# PERIPHERAL.net
KiCad netlist of a schematic drawn in Altium Designer
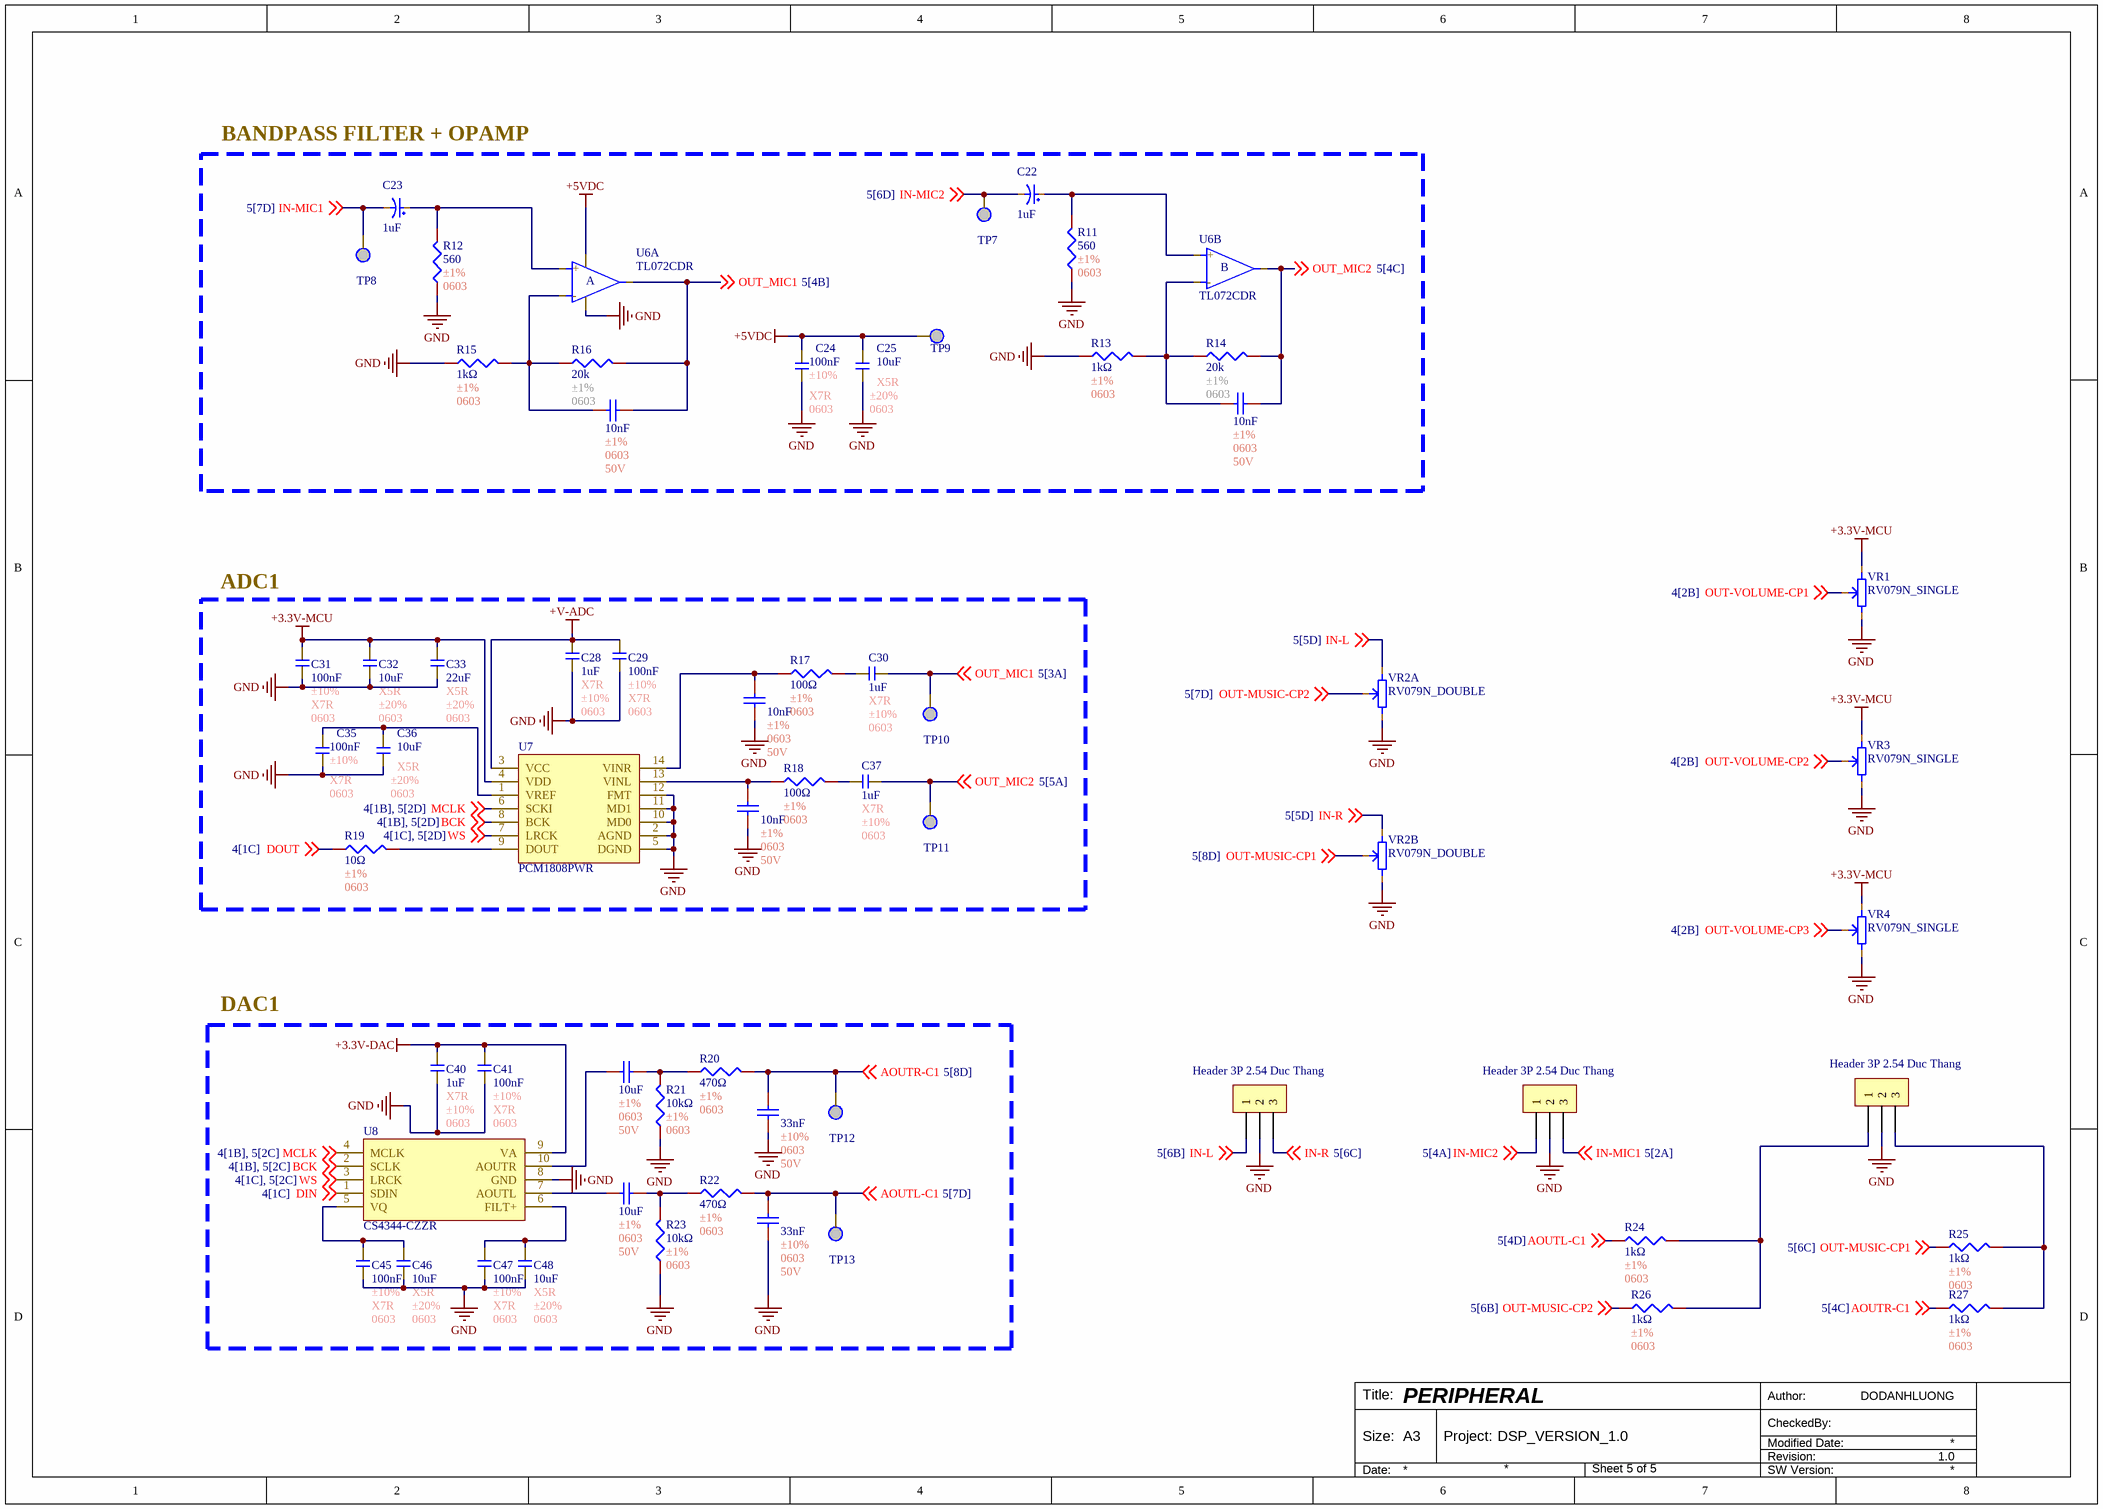
[diagram p0: PERIPHERAL.SchDoc]

(export (version "E")
  (design (tool "Eeschema 10.0.6"))
  (components
    (comp (ref "C22")
      (value "1uF")
      (footprint "C_TH_5x11mm")
      (description "10uF 50V ±20% Through Hole,D5xL11mm Aluminum Electrolytic Capacitors - Leaded ROHS")
      (fields (field (name "MANUFACTURER") "Rubycon") (field (name "MFR. PART #") "50YXF10MEFC5X11"))
      (libsource (lib "Capital") (part "C_10uF_5x11TH"))
    )
    (comp (ref "C23")
      (value "1uF")
      (footprint "C_TH_5x11mm")
      (description "10uF 50V ±20% Through Hole,D5xL11mm Aluminum Electrolytic Capacitors - Leaded ROHS")
      (fields (field (name "MANUFACTURER") "Rubycon") (field (name "MFR. PART #") "50YXF10MEFC5X11"))
      (libsource (lib "Capital") (part "C_10uF_5x11TH"))
    )
    (comp (ref "C24")
      (value "100nF")
      (footprint "C0603")
      (description "50V 100nF X7R ±10% 0603 Multilayer Ceramic Capacitors MLCC - SMD/SMT ROHS")
      (fields
        (field (name "MANUFACTURER") "YAGEO")
        (field (name "MFR. PART #") "CC0603KRX7R9BB104")
        (field (name "TOLERANCE") "±10%")
        (field (name "TEMPERATURE COEFFICIENT") "X7R")
        (field (name "PACKAGE") "0603")
      )
      (libsource (lib "DSP_VERSION_1.0") (part "C0603_100nF_±10%_X7R"))
    )
    (comp (ref "C25")
      (value "10uF")
      (footprint "C0603")
      (description "25V 10uF X5R ±20% 0603 Multilayer Ceramic Capacitors MLCC - SMD/SMT ROHS")
      (fields
        (field (name "MANUFACTURER") "YAGEO")
        (field (name "MFR. PART #") "CC0603MRX5R8BB106")
        (field (name "TEMPERATURE COEFFICIENT") "X5R")
        (field (name "TOLERANCE") "±20%")
        (field (name "PACKAGE") "0603")
      )
      (libsource (lib "DSP_VERSION_1.0") (part "C0603_10uF_±10%_X7R"))
    )
    (comp (ref "C26")
      (value "10nF")
      (footprint "C0603")
      (description "50V 10pF NP0 ±1% 0402 Multilayer Ceramic Capacitors MLCC - SMD/SMT ROHS")
      (fields
        (field (name "MANUFACTURER") "YAGEO")
        (field (name "MFR. PART #") "CC0402FRNPO9BN100")
        (field (name "TOLERANCE") "±1%")
        (field (name "PACKAGE") "0603")
        (field (name "VOLTAGE RATING") "50V")
      )
      (libsource (lib "Capital") (part "C0603_10nF_±1%"))
    )
    (comp (ref "C27")
      (value "10nF")
      (footprint "C0603")
      (description "50V 10pF NP0 ±1% 0402 Multilayer Ceramic Capacitors MLCC - SMD/SMT ROHS")
      (fields
        (field (name "MANUFACTURER") "YAGEO")
        (field (name "MFR. PART #") "CC0402FRNPO9BN100")
        (field (name "TOLERANCE") "±1%")
        (field (name "PACKAGE") "0603")
        (field (name "VOLTAGE RATING") "50V")
      )
      (libsource (lib "Capital") (part "C0603_10nF_±1%"))
    )
    (comp (ref "C28")
      (value "1uF")
      (footprint "C0603")
      (description "50V 1uF X7R ±10% 0603 Multilayer Ceramic Capacitors MLCC - SMD/SMT ROHS")
      (fields
        (field (name "MANUFACTURER") "YAGEO")
        (field (name "MFR. PART #") "CC0603KRX7R9BB105")
        (field (name "TEMPERATURE COEFFICIENT") "X7R")
        (field (name "TOLERANCE") "±10%")
        (field (name "PACKAGE") "0603")
      )
      (libsource (lib "DSP_VERSION_1.0") (part "C0603_1uF_±10%_X7R"))
    )
    (comp (ref "C29")
      (value "100nF")
      (footprint "C0603")
      (description "50V 100nF X7R ±10% 0603 Multilayer Ceramic Capacitors MLCC - SMD/SMT ROHS")
      (fields
        (field (name "MANUFACTURER") "YAGEO")
        (field (name "MFR. PART #") "CC0603KRX7R9BB104")
        (field (name "TOLERANCE") "±10%")
        (field (name "TEMPERATURE COEFFICIENT") "X7R")
        (field (name "PACKAGE") "0603")
      )
      (libsource (lib "DSP_VERSION_1.0") (part "C0603_100nF_±10%_X7R"))
    )
    (comp (ref "C30")
      (value "1uF")
      (footprint "C0603")
      (description "50V 1uF X7R ±10% 0603 Multilayer Ceramic Capacitors MLCC - SMD/SMT ROHS")
      (fields
        (field (name "MANUFACTURER") "YAGEO")
        (field (name "MFR. PART #") "CC0603KRX7R9BB105")
        (field (name "TEMPERATURE COEFFICIENT") "X7R")
        (field (name "TOLERANCE") "±10%")
        (field (name "PACKAGE") "0603")
      )
      (libsource (lib "DSP_VERSION_1.0") (part "C0603_1uF_±10%_X7R"))
    )
    (comp (ref "C31")
      (value "100nF")
      (footprint "C0603")
      (description "50V 100nF X7R ±10% 0603 Multilayer Ceramic Capacitors MLCC - SMD/SMT ROHS")
      (fields
        (field (name "MANUFACTURER") "YAGEO")
        (field (name "MFR. PART #") "CC0603KRX7R9BB104")
        (field (name "TOLERANCE") "±10%")
        (field (name "TEMPERATURE COEFFICIENT") "X7R")
        (field (name "PACKAGE") "0603")
      )
      (libsource (lib "DSP_VERSION_1.0") (part "C0603_100nF_±10%_X7R"))
    )
    (comp (ref "C32")
      (value "10uF")
      (footprint "C0603")
      (description "25V 10uF X5R ±20% 0603 Multilayer Ceramic Capacitors MLCC - SMD/SMT ROHS")
      (fields
        (field (name "MANUFACTURER") "YAGEO")
        (field (name "MFR. PART #") "CC0603MRX5R8BB106")
        (field (name "TEMPERATURE COEFFICIENT") "X5R")
        (field (name "TOLERANCE") "±20%")
        (field (name "PACKAGE") "0603")
      )
      (libsource (lib "DSP_VERSION_1.0") (part "C0603_10uF_±10%_X7R"))
    )
    (comp (ref "C33")
      (value "22uF")
      (footprint "C0603")
      (description "6.3V 22uF X5R ±20% 0603 Multilayer Ceramic Capacitors MLCC - SMD/SMT ROHS")
      (fields
        (field (name "MANUFACTURER") "YAGEO")
        (field (name "MFR. PART #") "CC0603MRX5R5BB226")
        (field (name "TEMPERATURE COEFFICIENT") "X5R")
        (field (name "TOLERANCE") "±20%")
        (field (name "PACKAGE") "0603")
      )
      (libsource (lib "DSP_VERSION_1.0") (part "C0603_22uF_±20%_X5R"))
    )
    (comp (ref "C34")
      (value "10nF")
      (footprint "C0603")
      (description "50V 10pF NP0 ±1% 0402 Multilayer Ceramic Capacitors MLCC - SMD/SMT ROHS")
      (fields
        (field (name "MANUFACTURER") "YAGEO")
        (field (name "MFR. PART #") "CC0402FRNPO9BN100")
        (field (name "TOLERANCE") "±1%")
        (field (name "PACKAGE") "0603")
        (field (name "VOLTAGE RATING") "50V")
      )
      (libsource (lib "Capital") (part "C0603_10nF_±1%"))
    )
    (comp (ref "C35")
      (value "100nF")
      (footprint "C0603")
      (description "50V 100nF X7R ±10% 0603 Multilayer Ceramic Capacitors MLCC - SMD/SMT ROHS")
      (fields
        (field (name "MANUFACTURER") "YAGEO")
        (field (name "MFR. PART #") "CC0603KRX7R9BB104")
        (field (name "TOLERANCE") "±10%")
        (field (name "TEMPERATURE COEFFICIENT") "X7R")
        (field (name "PACKAGE") "0603")
      )
      (libsource (lib "DSP_VERSION_1.0") (part "C0603_100nF_±10%_X7R"))
    )
    (comp (ref "C36")
      (value "10uF")
      (footprint "C0603")
      (description "25V 10uF X5R ±20% 0603 Multilayer Ceramic Capacitors MLCC - SMD/SMT ROHS")
      (fields
        (field (name "MANUFACTURER") "YAGEO")
        (field (name "MFR. PART #") "CC0603MRX5R8BB106")
        (field (name "TEMPERATURE COEFFICIENT") "X5R")
        (field (name "TOLERANCE") "±20%")
        (field (name "PACKAGE") "0603")
      )
      (libsource (lib "DSP_VERSION_1.0") (part "C0603_10uF_±10%_X7R"))
    )
    (comp (ref "C37")
      (value "1uF")
      (footprint "C0603")
      (description "50V 1uF X7R ±10% 0603 Multilayer Ceramic Capacitors MLCC - SMD/SMT ROHS")
      (fields
        (field (name "MANUFACTURER") "YAGEO")
        (field (name "MFR. PART #") "CC0603KRX7R9BB105")
        (field (name "TEMPERATURE COEFFICIENT") "X7R")
        (field (name "TOLERANCE") "±10%")
        (field (name "PACKAGE") "0603")
      )
      (libsource (lib "DSP_VERSION_1.0") (part "C0603_1uF_±10%_X7R"))
    )
    (comp (ref "C38")
      (value "10nF")
      (footprint "C0603")
      (description "50V 10pF NP0 ±1% 0402 Multilayer Ceramic Capacitors MLCC - SMD/SMT ROHS")
      (fields
        (field (name "MANUFACTURER") "YAGEO")
        (field (name "MFR. PART #") "CC0402FRNPO9BN100")
        (field (name "TOLERANCE") "±1%")
        (field (name "PACKAGE") "0603")
        (field (name "VOLTAGE RATING") "50V")
      )
      (libsource (lib "Capital") (part "C0603_10nF_±1%"))
    )
    (comp (ref "C39")
      (value "10uF")
      (footprint "C0603")
      (description "50V 10pF NP0 ±1% 0402 Multilayer Ceramic Capacitors MLCC - SMD/SMT ROHS")
      (fields
        (field (name "MANUFACTURER") "YAGEO")
        (field (name "MFR. PART #") "CC0402FRNPO9BN100")
        (field (name "TOLERANCE") "±1%")
        (field (name "PACKAGE") "0603")
        (field (name "VOLTAGE RATING") "50V")
      )
      (libsource (lib "Capital") (part "C0603_10uF_±1%"))
    )
    (comp (ref "C40")
      (value "1uF")
      (footprint "C0603")
      (description "50V 1uF X7R ±10% 0603 Multilayer Ceramic Capacitors MLCC - SMD/SMT ROHS")
      (fields
        (field (name "MANUFACTURER") "YAGEO")
        (field (name "MFR. PART #") "CC0603KRX7R9BB105")
        (field (name "TEMPERATURE COEFFICIENT") "X7R")
        (field (name "TOLERANCE") "±10%")
        (field (name "PACKAGE") "0603")
      )
      (libsource (lib "DSP_VERSION_1.0") (part "C0603_1uF_±10%_X7R"))
    )
    (comp (ref "C41")
      (value "100nF")
      (footprint "C0603")
      (description "50V 100nF X7R ±10% 0603 Multilayer Ceramic Capacitors MLCC - SMD/SMT ROHS")
      (fields
        (field (name "MANUFACTURER") "YAGEO")
        (field (name "MFR. PART #") "CC0603KRX7R9BB104")
        (field (name "TOLERANCE") "±10%")
        (field (name "TEMPERATURE COEFFICIENT") "X7R")
        (field (name "PACKAGE") "0603")
      )
      (libsource (lib "DSP_VERSION_1.0") (part "C0603_100nF_±10%_X7R"))
    )
    (comp (ref "C42")
      (value "33nF")
      (footprint "C0603")
      (description "100mW Thick Film Resistor 75V ±100ppm/℃ ±1% 470Ω 0603 Chip Resistor - Surface Mount ROHS")
      (fields
        (field (name "MANUFACTURER") "YAGEO")
        (field (name "MFR. PART #") "CC0603KRX7R9BB333")
        (field (name "TOLERANCE") "±10%")
        (field (name "PACKAGE") "0603")
        (field (name "VOLTAGE RATING") "50V")
      )
      (libsource (lib "Capital") (part "C0603_33nF_±10%"))
    )
    (comp (ref "C43")
      (value "10uF")
      (footprint "C0603")
      (description "50V 10pF NP0 ±1% 0402 Multilayer Ceramic Capacitors MLCC - SMD/SMT ROHS")
      (fields
        (field (name "MANUFACTURER") "YAGEO")
        (field (name "MFR. PART #") "CC0402FRNPO9BN100")
        (field (name "TOLERANCE") "±1%")
        (field (name "PACKAGE") "0603")
        (field (name "VOLTAGE RATING") "50V")
      )
      (libsource (lib "Capital") (part "C0603_10uF_±1%"))
    )
    (comp (ref "C44")
      (value "33nF")
      (footprint "C0603")
      (description "100mW Thick Film Resistor 75V ±100ppm/℃ ±1% 470Ω 0603 Chip Resistor - Surface Mount ROHS")
      (fields
        (field (name "MANUFACTURER") "YAGEO")
        (field (name "MFR. PART #") "CC0603KRX7R9BB333")
        (field (name "TOLERANCE") "±10%")
        (field (name "PACKAGE") "0603")
        (field (name "VOLTAGE RATING") "50V")
      )
      (libsource (lib "Capital") (part "C0603_33nF_±10%"))
    )
    (comp (ref "C45")
      (value "100nF")
      (footprint "C0603")
      (description "50V 100nF X7R ±10% 0603 Multilayer Ceramic Capacitors MLCC - SMD/SMT ROHS")
      (fields
        (field (name "MANUFACTURER") "YAGEO")
        (field (name "MFR. PART #") "CC0603KRX7R9BB104")
        (field (name "TOLERANCE") "±10%")
        (field (name "TEMPERATURE COEFFICIENT") "X7R")
        (field (name "PACKAGE") "0603")
      )
      (libsource (lib "DSP_VERSION_1.0") (part "C0603_100nF_±10%_X7R"))
    )
    (comp (ref "C46")
      (value "10uF")
      (footprint "C0603")
      (description "25V 10uF X5R ±20% 0603 Multilayer Ceramic Capacitors MLCC - SMD/SMT ROHS")
      (fields
        (field (name "MANUFACTURER") "YAGEO")
        (field (name "MFR. PART #") "CC0603MRX5R8BB106")
        (field (name "TEMPERATURE COEFFICIENT") "X5R")
        (field (name "TOLERANCE") "±20%")
        (field (name "PACKAGE") "0603")
      )
      (libsource (lib "DSP_VERSION_1.0") (part "C0603_10uF_±10%_X7R"))
    )
    (comp (ref "C47")
      (value "100nF")
      (footprint "C0603")
      (description "50V 100nF X7R ±10% 0603 Multilayer Ceramic Capacitors MLCC - SMD/SMT ROHS")
      (fields
        (field (name "MANUFACTURER") "YAGEO")
        (field (name "MFR. PART #") "CC0603KRX7R9BB104")
        (field (name "TOLERANCE") "±10%")
        (field (name "TEMPERATURE COEFFICIENT") "X7R")
        (field (name "PACKAGE") "0603")
      )
      (libsource (lib "DSP_VERSION_1.0") (part "C0603_100nF_±10%_X7R"))
    )
    (comp (ref "C48")
      (value "10uF")
      (footprint "C0603")
      (description "25V 10uF X5R ±20% 0603 Multilayer Ceramic Capacitors MLCC - SMD/SMT ROHS")
      (fields
        (field (name "MANUFACTURER") "YAGEO")
        (field (name "MFR. PART #") "CC0603MRX5R8BB106")
        (field (name "TEMPERATURE COEFFICIENT") "X5R")
        (field (name "TOLERANCE") "±20%")
        (field (name "PACKAGE") "0603")
      )
      (libsource (lib "DSP_VERSION_1.0") (part "C0603_10uF_±10%_X7R"))
    )
    (comp (ref "H1")
      (value "Header 3P 2.54 Duc Thang")
      (footprint "XH2.54M-3")
      (description "Cắm")
      (libsource (lib "Header") (part "Header 3P 2.54 Duc Thang"))
    )
    (comp (ref "H2")
      (value "Header 3P 2.54 Duc Thang")
      (footprint "XH2.54M-3")
      (description "Cắm")
      (libsource (lib "Header") (part "Header 3P 2.54 Duc Thang"))
    )
    (comp (ref "H3")
      (value "Header 3P 2.54 Duc Thang")
      (footprint "XH2.54M-3")
      (description "Cắm")
      (libsource (lib "Header") (part "Header 3P 2.54 Duc Thang"))
    )
    (comp (ref "R11")
      (value "560")
      (footprint "R0603")
      (description "62.5mW Thick Film Resistor 50V ±1% ±200ppm/℃ 10Ω 0402 Chip Resistor - Surface Mount ROHS")
      (fields
        (field (name "MANUFACTURER") "YAGEO")
        (field (name "MFR. PART #") "RC0402FR-0710RL")
        (field (name "TOLERANCE") "±1%")
        (field (name "PACKAGE") "0603")
      )
      (libsource (lib "Resistor") (part "R0603_10kΩ_±1%"))
    )
    (comp (ref "R12")
      (value "560")
      (footprint "R0603")
      (description "62.5mW Thick Film Resistor 50V ±1% ±200ppm/℃ 10Ω 0402 Chip Resistor - Surface Mount ROHS")
      (fields
        (field (name "MANUFACTURER") "YAGEO")
        (field (name "MFR. PART #") "RC0402FR-0710RL")
        (field (name "TOLERANCE") "±1%")
        (field (name "PACKAGE") "0603")
      )
      (libsource (lib "Resistor") (part "R0603_10kΩ_±1%"))
    )
    (comp (ref "R13")
      (value "1kΩ")
      (footprint "R0603")
      (description "62.5mW Thick Film Resistor 50V ±1% ±200ppm/℃ 10Ω 0402 Chip Resistor - Surface Mount ROHS")
      (fields
        (field (name "MANUFACTURER") "YAGEO")
        (field (name "MFR. PART #") "RC0402FR-0710RL")
        (field (name "TOLERANCE") "±1%")
        (field (name "PACKAGE") "0603")
      )
      (libsource (lib "Resistor") (part "R0603_1kΩ_±1%"))
    )
    (comp (ref "R14")
      (value "20k")
      (footprint "R0603")
      (description "100mW Thick Film Resistor 75V ±100ppm/℃ ±1% 5.1kΩ 0603 Chip Resistor - Surface Mount ROHS")
      (fields
        (field (name "MANUFACTURER") "FOJAN")
        (field (name "MFR. PART #") "FRC0603F5101TS")
        (field (name "TOLERANCE") "±1%")
        (field (name "PACKAGE") "0603")
      )
      (libsource (lib "Resistor") (part "R0603_5k1Ω_±1%"))
    )
    (comp (ref "R15")
      (value "1kΩ")
      (footprint "R0603")
      (description "62.5mW Thick Film Resistor 50V ±1% ±200ppm/℃ 10Ω 0402 Chip Resistor - Surface Mount ROHS")
      (fields
        (field (name "MANUFACTURER") "YAGEO")
        (field (name "MFR. PART #") "RC0402FR-0710RL")
        (field (name "TOLERANCE") "±1%")
        (field (name "PACKAGE") "0603")
      )
      (libsource (lib "Resistor") (part "R0603_1kΩ_±1%"))
    )
    (comp (ref "R16")
      (value "20k")
      (footprint "R0603")
      (description "100mW Thick Film Resistor 75V ±100ppm/℃ ±1% 5.1kΩ 0603 Chip Resistor - Surface Mount ROHS")
      (fields
        (field (name "MANUFACTURER") "FOJAN")
        (field (name "MFR. PART #") "FRC0603F5101TS")
        (field (name "TOLERANCE") "±1%")
        (field (name "PACKAGE") "0603")
      )
      (libsource (lib "Resistor") (part "R0603_5k1Ω_±1%"))
    )
    (comp (ref "R17")
      (value "100Ω")
      (footprint "R0603")
      (description "62.5mW Thick Film Resistor 50V ±1% ±200ppm/℃ 10Ω 0402 Chip Resistor - Surface Mount ROHS")
      (fields
        (field (name "MANUFACTURER") "YAGEO")
        (field (name "MFR. PART #") "RC0402FR-0710RL")
        (field (name "TOLERANCE") "±1%")
        (field (name "PACKAGE") "0603")
      )
      (libsource (lib "Resistor") (part "R0603_100Ω_±1%"))
    )
    (comp (ref "R18")
      (value "100Ω")
      (footprint "R0603")
      (description "62.5mW Thick Film Resistor 50V ±1% ±200ppm/℃ 10Ω 0402 Chip Resistor - Surface Mount ROHS")
      (fields
        (field (name "MANUFACTURER") "YAGEO")
        (field (name "MFR. PART #") "RC0402FR-0710RL")
        (field (name "TOLERANCE") "±1%")
        (field (name "PACKAGE") "0603")
      )
      (libsource (lib "Resistor") (part "R0603_100Ω_±1%"))
    )
    (comp (ref "R19")
      (value "10Ω")
      (footprint "R0603")
      (description "62.5mW Thick Film Resistor 50V ±1% ±200ppm/℃ 10Ω 0402 Chip Resistor - Surface Mount ROHS")
      (fields
        (field (name "MANUFACTURER") "YAGEO")
        (field (name "MFR. PART #") "RC0402FR-0710RL")
        (field (name "TOLERANCE") "±1%")
        (field (name "PACKAGE") "0603")
      )
      (libsource (lib "Resistor") (part "R0603_10Ω_±1%"))
    )
    (comp (ref "R20")
      (value "470Ω")
      (footprint "R0603")
      (description "62.5mW Thick Film Resistor 50V ±1% ±200ppm/℃ 10Ω 0402 Chip Resistor - Surface Mount ROHS")
      (fields
        (field (name "MANUFACTURER") "YAGEO")
        (field (name "MFR. PART #") "RC0603FR-07470RL")
        (field (name "TOLERANCE") "±1%")
        (field (name "PACKAGE") "0603")
      )
      (libsource (lib "Resistor") (part "R0603_470Ω_±1%_1"))
    )
    (comp (ref "R21")
      (value "10kΩ")
      (footprint "R0603")
      (description "62.5mW Thick Film Resistor 50V ±1% ±200ppm/℃ 10Ω 0402 Chip Resistor - Surface Mount ROHS")
      (fields
        (field (name "MANUFACTURER") "YAGEO")
        (field (name "MFR. PART #") "RC0402FR-0710RL")
        (field (name "TOLERANCE") "±1%")
        (field (name "PACKAGE") "0603")
      )
      (libsource (lib "Resistor") (part "R0603_10kΩ_±1%"))
    )
    (comp (ref "R22")
      (value "470Ω")
      (footprint "R0603")
      (description "62.5mW Thick Film Resistor 50V ±1% ±200ppm/℃ 10Ω 0402 Chip Resistor - Surface Mount ROHS")
      (fields
        (field (name "MANUFACTURER") "YAGEO")
        (field (name "MFR. PART #") "RC0603FR-07470RL")
        (field (name "TOLERANCE") "±1%")
        (field (name "PACKAGE") "0603")
      )
      (libsource (lib "Resistor") (part "R0603_470Ω_±1%_1"))
    )
    (comp (ref "R23")
      (value "10kΩ")
      (footprint "R0603")
      (description "62.5mW Thick Film Resistor 50V ±1% ±200ppm/℃ 10Ω 0402 Chip Resistor - Surface Mount ROHS")
      (fields
        (field (name "MANUFACTURER") "YAGEO")
        (field (name "MFR. PART #") "RC0402FR-0710RL")
        (field (name "TOLERANCE") "±1%")
        (field (name "PACKAGE") "0603")
      )
      (libsource (lib "Resistor") (part "R0603_10kΩ_±1%"))
    )
    (comp (ref "R24")
      (value "1kΩ")
      (footprint "R0603")
      (description "62.5mW Thick Film Resistor 50V ±1% ±200ppm/℃ 10Ω 0402 Chip Resistor - Surface Mount ROHS")
      (fields
        (field (name "MANUFACTURER") "YAGEO")
        (field (name "MFR. PART #") "RC0402FR-0710RL")
        (field (name "TOLERANCE") "±1%")
        (field (name "PACKAGE") "0603")
      )
      (libsource (lib "Resistor") (part "R0603_1kΩ_±1%"))
    )
    (comp (ref "R25")
      (value "1kΩ")
      (footprint "R0603")
      (description "62.5mW Thick Film Resistor 50V ±1% ±200ppm/℃ 10Ω 0402 Chip Resistor - Surface Mount ROHS")
      (fields
        (field (name "MANUFACTURER") "YAGEO")
        (field (name "MFR. PART #") "RC0402FR-0710RL")
        (field (name "TOLERANCE") "±1%")
        (field (name "PACKAGE") "0603")
      )
      (libsource (lib "Resistor") (part "R0603_1kΩ_±1%"))
    )
    (comp (ref "R26")
      (value "1kΩ")
      (footprint "R0603")
      (description "62.5mW Thick Film Resistor 50V ±1% ±200ppm/℃ 10Ω 0402 Chip Resistor - Surface Mount ROHS")
      (fields
        (field (name "MANUFACTURER") "YAGEO")
        (field (name "MFR. PART #") "RC0402FR-0710RL")
        (field (name "TOLERANCE") "±1%")
        (field (name "PACKAGE") "0603")
      )
      (libsource (lib "Resistor") (part "R0603_1kΩ_±1%"))
    )
    (comp (ref "R27")
      (value "1kΩ")
      (footprint "R0603")
      (description "62.5mW Thick Film Resistor 50V ±1% ±200ppm/℃ 10Ω 0402 Chip Resistor - Surface Mount ROHS")
      (fields
        (field (name "MANUFACTURER") "YAGEO")
        (field (name "MFR. PART #") "RC0402FR-0710RL")
        (field (name "TOLERANCE") "±1%")
        (field (name "PACKAGE") "0603")
      )
      (libsource (lib "Resistor") (part "R0603_1kΩ_±1%"))
    )
    (comp (ref "TP7") (value "TP") (footprint "TP") (libsource (lib "Other") (part "TP")))
    (comp (ref "TP8") (value "TP") (footprint "TP") (libsource (lib "Other") (part "TP")))
    (comp (ref "TP9") (value "TP") (footprint "TP") (libsource (lib "Other") (part "TP")))
    (comp (ref "TP10") (value "TP") (footprint "TP") (libsource (lib "Other") (part "TP")))
    (comp (ref "TP11") (value "TP") (footprint "TP") (libsource (lib "Other") (part "TP")))
    (comp (ref "TP12") (value "TP") (footprint "TP") (libsource (lib "Other") (part "TP")))
    (comp (ref "TP13") (value "TP") (footprint "TP") (libsource (lib "Other") (part "TP")))
    (comp (ref "U6")
      (value "TL072CDR")
      (footprint "TL072CDR")
      (description "3mV 65pA 3MHz 13V/us 2 SOIC-8 FET Input Amplifiers ROHS")
      (fields (field (name "MANUFACTURER") "TI") (field (name "LCSC PART #") "C67473"))
      (libsource (lib "IC") (part "TL072CDR"))
    )
    (comp (ref "U7")
      (value "PCM1808PWR")
      (footprint "PCM1808PWR")
      (description "4.5V~5.5V 24 I2S TSSOP-14 ADCs/DACs - Special Purpose ROHS")
      (fields (field (name "MANUFACTURER") "TI") (field (name "LCSC PART #") "C55513"))
      (libsource (lib "IC") (part "PCM1808PWR"))
    )
    (comp (ref "U8")
      (value "CS4344-CZZR")
      (footprint "CS4344-CZZR")
      (description "250ms I2S 3.3V~5V 24 TSSOP-10-3mm Digital to Analog Converters (DAC) ROHS")
      (fields (field (name "MANUFACTURER") "Cirrus Logic") (field (name "LCSC PART #") "C8952"))
      (libsource (lib "IC") (part "CS4344-CZZR"))
    )
    (comp (ref "VR1")
      (value "RV079N_SINGLE")
      (footprint "RK079N_SINGLE")
      (libsource (lib "Resistor") (part "RV079N_SINGLE"))
    )
    (comp (ref "VR2")
      (value "RV079N_DOUBLE")
      (footprint "RK079N_DOUBLE")
      (libsource (lib "Resistor") (part "RV079N_DOUBLE"))
    )
    (comp (ref "VR3")
      (value "RV079N_SINGLE")
      (footprint "RK079N_SINGLE")
      (libsource (lib "Resistor") (part "RV079N_SINGLE"))
    )
    (comp (ref "VR4")
      (value "RV079N_SINGLE")
      (footprint "RK079N_SINGLE")
      (libsource (lib "Resistor") (part "RV079N_SINGLE"))
    )
  )
  (nets
    (net (code "1") (name "+3.3V-DAC") (class "Default")
      (node (ref "C40") (pin "2") (pinfunction "2_2") (pintype "passive"))
      (node (ref "C41") (pin "2") (pinfunction "2_2") (pintype "passive"))
      (node (ref "U8") (pin "9") (pinfunction "VA_9") (pintype "passive"))
    )
    (net (code "2") (name "+3.3V-MCU") (class "Default")
      (node (ref "C31") (pin "2") (pinfunction "2_2") (pintype "passive"))
      (node (ref "C32") (pin "2") (pinfunction "2_2") (pintype "passive"))
      (node (ref "C33") (pin "2") (pinfunction "2_2") (pintype "passive"))
      (node (ref "U7") (pin "4") (pinfunction "VDD_4") (pintype "passive"))
      (node (ref "VR1") (pin "3") (pinfunction "3_3") (pintype "passive"))
      (node (ref "VR3") (pin "3") (pinfunction "3_3") (pintype "passive"))
      (node (ref "VR4") (pin "3") (pinfunction "3_3") (pintype "passive"))
    )
    (net (code "3") (name "+5VDC") (class "Default")
      (node (ref "C24") (pin "2") (pinfunction "2_2") (pintype "passive"))
      (node (ref "C25") (pin "2") (pinfunction "2_2") (pintype "passive"))
      (node (ref "TP9") (pin "1") (pinfunction "1_1") (pintype "passive"))
      (node (ref "U6") (pin "8") (pinfunction "8_8") (pintype "passive"))
    )
    (net (code "4") (name "+V-ADC") (class "Default")
      (node (ref "C28") (pin "2") (pinfunction "2_2") (pintype "passive"))
      (node (ref "C29") (pin "2") (pinfunction "2_2") (pintype "passive"))
      (node (ref "U7") (pin "3") (pinfunction "VCC_3") (pintype "passive"))
    )
    (net (code "5") (name "AOUTL-C1") (class "Default")
      (node (ref "C44") (pin "1") (pinfunction "1_1") (pintype "passive"))
      (node (ref "R22") (pin "2") (pinfunction "2_2") (pintype "passive"))
      (node (ref "R24") (pin "1") (pinfunction "1_1") (pintype "passive"))
      (node (ref "TP13") (pin "1") (pinfunction "1_1") (pintype "passive"))
    )
    (net (code "6") (name "AOUTR-C1") (class "Default")
      (node (ref "C42") (pin "1") (pinfunction "1_1") (pintype "passive"))
      (node (ref "R20") (pin "2") (pinfunction "2_2") (pintype "passive"))
      (node (ref "R27") (pin "1") (pinfunction "1_1") (pintype "passive"))
      (node (ref "TP12") (pin "1") (pinfunction "1_1") (pintype "passive"))
    )
    (net (code "7") (name "BCK") (class "Default")
      (node (ref "U7") (pin "8") (pinfunction "BCK_8") (pintype "passive"))
      (node (ref "U8") (pin "2") (pinfunction "SCLK_2") (pintype "passive"))
    )
    (net (code "8") (name "DIN") (class "Default")
      (node (ref "U8") (pin "1") (pinfunction "SDIN_1") (pintype "passive"))
    )
    (net (code "9") (name "DOUT") (class "Default")
      (node (ref "R19") (pin "1") (pinfunction "1_1") (pintype "passive"))
    )
    (net (code "10") (name "GND") (class "Default")
      (node (ref "C24") (pin "1") (pinfunction "1_1") (pintype "passive"))
      (node (ref "C25") (pin "1") (pinfunction "1_1") (pintype "passive"))
      (node (ref "C28") (pin "1") (pinfunction "1_1") (pintype "passive"))
      (node (ref "C29") (pin "1") (pinfunction "1_1") (pintype "passive"))
      (node (ref "C31") (pin "1") (pinfunction "1_1") (pintype "passive"))
      (node (ref "C32") (pin "1") (pinfunction "1_1") (pintype "passive"))
      (node (ref "C33") (pin "1") (pinfunction "1_1") (pintype "passive"))
      (node (ref "C34") (pin "2") (pinfunction "2_2") (pintype "passive"))
      (node (ref "C35") (pin "1") (pinfunction "1_1") (pintype "passive"))
      (node (ref "C36") (pin "1") (pinfunction "1_1") (pintype "passive"))
      (node (ref "C38") (pin "2") (pinfunction "2_2") (pintype "passive"))
      (node (ref "C40") (pin "1") (pinfunction "1_1") (pintype "passive"))
      (node (ref "C41") (pin "1") (pinfunction "1_1") (pintype "passive"))
      (node (ref "C42") (pin "2") (pinfunction "2_2") (pintype "passive"))
      (node (ref "C44") (pin "2") (pinfunction "2_2") (pintype "passive"))
      (node (ref "C45") (pin "1") (pinfunction "1_1") (pintype "passive"))
      (node (ref "C46") (pin "1") (pinfunction "1_1") (pintype "passive"))
      (node (ref "C47") (pin "1") (pinfunction "1_1") (pintype "passive"))
      (node (ref "C48") (pin "1") (pinfunction "1_1") (pintype "passive"))
      (node (ref "H1") (pin "2") (pinfunction "2_2") (pintype "passive"))
      (node (ref "H2") (pin "2") (pinfunction "2_2") (pintype "passive"))
      (node (ref "H3") (pin "2") (pinfunction "2_2") (pintype "passive"))
      (node (ref "R11") (pin "1") (pinfunction "1_1") (pintype "passive"))
      (node (ref "R12") (pin "1") (pinfunction "1_1") (pintype "passive"))
      (node (ref "R13") (pin "1") (pinfunction "1_1") (pintype "passive"))
      (node (ref "R15") (pin "1") (pinfunction "1_1") (pintype "passive"))
      (node (ref "R21") (pin "1") (pinfunction "1_1") (pintype "passive"))
      (node (ref "R23") (pin "1") (pinfunction "1_1") (pintype "passive"))
      (node (ref "U6") (pin "4") (pinfunction "GND_4") (pintype "passive"))
      (node (ref "U7") (pin "10") (pinfunction "MD0_10") (pintype "passive"))
      (node (ref "U7") (pin "11") (pinfunction "MD1_11") (pintype "passive"))
      (node (ref "U7") (pin "12") (pinfunction "FMT_12") (pintype "passive"))
      (node (ref "U7") (pin "2") (pinfunction "AGND_2") (pintype "passive"))
      (node (ref "U7") (pin "5") (pinfunction "DGND_5") (pintype "passive"))
      (node (ref "U8") (pin "8") (pinfunction "GND_8") (pintype "passive"))
      (node (ref "VR1") (pin "1") (pinfunction "1_1") (pintype "passive"))
      (node (ref "VR2") (pin "1") (pinfunction "1_1") (pintype "passive"))
      (node (ref "VR2") (pin "4") (pinfunction "4_4") (pintype "passive"))
      (node (ref "VR3") (pin "1") (pinfunction "1_1") (pintype "passive"))
      (node (ref "VR4") (pin "1") (pinfunction "1_1") (pintype "passive"))
    )
    (net (code "11") (name "IN-L") (class "Default")
      (node (ref "H2") (pin "1") (pinfunction "1_1") (pintype "passive"))
      (node (ref "VR2") (pin "3") (pinfunction "3_3") (pintype "passive"))
    )
    (net (code "12") (name "IN-MIC1") (class "Default")
      (node (ref "C23") (pin "2") (pinfunction "2_2") (pintype "passive"))
      (node (ref "H3") (pin "3") (pinfunction "3_3") (pintype "passive"))
      (node (ref "TP8") (pin "1") (pinfunction "1_1") (pintype "passive"))
    )
    (net (code "13") (name "IN-MIC2") (class "Default")
      (node (ref "C22") (pin "2") (pinfunction "2_2") (pintype "passive"))
      (node (ref "H3") (pin "1") (pinfunction "1_1") (pintype "passive"))
      (node (ref "TP7") (pin "1") (pinfunction "1_1") (pintype "passive"))
    )
    (net (code "14") (name "IN-R") (class "Default")
      (node (ref "H2") (pin "3") (pinfunction "3_3") (pintype "passive"))
      (node (ref "VR2") (pin "6") (pinfunction "6_6") (pintype "passive"))
    )
    (net (code "15") (name "MCLK") (class "Default")
      (node (ref "U7") (pin "6") (pinfunction "SCKI_6") (pintype "passive"))
      (node (ref "U8") (pin "4") (pinfunction "MCLK_4") (pintype "passive"))
    )
    (net (code "16") (name "Net-(C30-Pad2)") (class "Default")
      (node (ref "C30") (pin "2") (pinfunction "2_2") (pintype "passive"))
      (node (ref "R17") (pin "2") (pinfunction "2_2") (pintype "passive"))
    )
    (net (code "17") (name "Net-(C37-Pad2)") (class "Default")
      (node (ref "C37") (pin "2") (pinfunction "2_2") (pintype "passive"))
      (node (ref "R18") (pin "2") (pinfunction "2_2") (pintype "passive"))
    )
    (net (code "18") (name "Net-(C39-Pad1)") (class "Default")
      (node (ref "C39") (pin "1") (pinfunction "1_1") (pintype "passive"))
      (node (ref "R20") (pin "1") (pinfunction "1_1") (pintype "passive"))
      (node (ref "R21") (pin "2") (pinfunction "2_2") (pintype "passive"))
    )
    (net (code "19") (name "Net-(C43-Pad1)") (class "Default")
      (node (ref "C43") (pin "1") (pinfunction "1_1") (pintype "passive"))
      (node (ref "R22") (pin "1") (pinfunction "1_1") (pintype "passive"))
      (node (ref "R23") (pin "2") (pinfunction "2_2") (pintype "passive"))
    )
    (net (code "20") (name "Net-(H1-Pad1)") (class "Default")
      (node (ref "H1") (pin "1") (pinfunction "1_1") (pintype "passive"))
      (node (ref "R24") (pin "2") (pinfunction "2_2") (pintype "passive"))
      (node (ref "R26") (pin "2") (pinfunction "2_2") (pintype "passive"))
    )
    (net (code "21") (name "Net-(H1-Pad3)") (class "Default")
      (node (ref "H1") (pin "3") (pinfunction "3_3") (pintype "passive"))
      (node (ref "R25") (pin "2") (pinfunction "2_2") (pintype "passive"))
      (node (ref "R27") (pin "2") (pinfunction "2_2") (pintype "passive"))
    )
    (net (code "22") (name "Net-(U6A-+)") (class "Default")
      (node (ref "C23") (pin "1") (pinfunction "1_1") (pintype "passive"))
      (node (ref "R12") (pin "2") (pinfunction "2_2") (pintype "passive"))
      (node (ref "U6") (pin "3") (pinfunction "+_3") (pintype "passive"))
    )
    (net (code "23") (name "Net-(U6A--)") (class "Default")
      (node (ref "C27") (pin "1") (pinfunction "1_1") (pintype "passive"))
      (node (ref "R15") (pin "2") (pinfunction "2_2") (pintype "passive"))
      (node (ref "R16") (pin "1") (pinfunction "1_1") (pintype "passive"))
      (node (ref "U6") (pin "2") (pinfunction "-_2") (pintype "passive"))
    )
    (net (code "24") (name "Net-(U6B-+)") (class "Default")
      (node (ref "C22") (pin "1") (pinfunction "1_1") (pintype "passive"))
      (node (ref "R11") (pin "2") (pinfunction "2_2") (pintype "passive"))
      (node (ref "U6") (pin "5") (pinfunction "+_5") (pintype "passive"))
    )
    (net (code "25") (name "Net-(U6B--)") (class "Default")
      (node (ref "C26") (pin "1") (pinfunction "1_1") (pintype "passive"))
      (node (ref "R13") (pin "2") (pinfunction "2_2") (pintype "passive"))
      (node (ref "R14") (pin "1") (pinfunction "1_1") (pintype "passive"))
      (node (ref "U6") (pin "6") (pinfunction "-_6") (pintype "passive"))
    )
    (net (code "26") (name "Net-(U7-DOUT)") (class "Default")
      (node (ref "R19") (pin "2") (pinfunction "2_2") (pintype "passive"))
      (node (ref "U7") (pin "9") (pinfunction "DOUT_9") (pintype "passive"))
    )
    (net (code "27") (name "Net-(U7-VINL)") (class "Default")
      (node (ref "C38") (pin "1") (pinfunction "1_1") (pintype "passive"))
      (node (ref "R18") (pin "1") (pinfunction "1_1") (pintype "passive"))
      (node (ref "U7") (pin "13") (pinfunction "VINL_13") (pintype "passive"))
    )
    (net (code "28") (name "Net-(U7-VINR)") (class "Default")
      (node (ref "C34") (pin "1") (pinfunction "1_1") (pintype "passive"))
      (node (ref "R17") (pin "1") (pinfunction "1_1") (pintype "passive"))
      (node (ref "U7") (pin "14") (pinfunction "VINR_14") (pintype "passive"))
    )
    (net (code "29") (name "Net-(U7-VREF)") (class "Default")
      (node (ref "C35") (pin "2") (pinfunction "2_2") (pintype "passive"))
      (node (ref "C36") (pin "2") (pinfunction "2_2") (pintype "passive"))
      (node (ref "U7") (pin "1") (pinfunction "VREF_1") (pintype "passive"))
    )
    (net (code "30") (name "Net-(U8-AOUTL)") (class "Default")
      (node (ref "C43") (pin "2") (pinfunction "2_2") (pintype "passive"))
      (node (ref "U8") (pin "7") (pinfunction "AOUTL_7") (pintype "passive"))
    )
    (net (code "31") (name "Net-(U8-AOUTR)") (class "Default")
      (node (ref "C39") (pin "2") (pinfunction "2_2") (pintype "passive"))
      (node (ref "U8") (pin "10") (pinfunction "AOUTR_10") (pintype "passive"))
    )
    (net (code "32") (name "Net-(U8-FILT+)") (class "Default")
      (node (ref "C47") (pin "2") (pinfunction "2_2") (pintype "passive"))
      (node (ref "C48") (pin "2") (pinfunction "2_2") (pintype "passive"))
      (node (ref "U8") (pin "6") (pinfunction "FILT+_6") (pintype "passive"))
    )
    (net (code "33") (name "Net-(U8-VQ)") (class "Default")
      (node (ref "C45") (pin "2") (pinfunction "2_2") (pintype "passive"))
      (node (ref "C46") (pin "2") (pinfunction "2_2") (pintype "passive"))
      (node (ref "U8") (pin "5") (pinfunction "VQ_5") (pintype "passive"))
    )
    (net (code "34") (name "OUT-MUSIC-CP1") (class "Default")
      (node (ref "R25") (pin "1") (pinfunction "1_1") (pintype "passive"))
      (node (ref "VR2") (pin "5") (pinfunction "5_5") (pintype "passive"))
    )
    (net (code "35") (name "OUT-MUSIC-CP2") (class "Default")
      (node (ref "R26") (pin "1") (pinfunction "1_1") (pintype "passive"))
      (node (ref "VR2") (pin "2") (pinfunction "2_2") (pintype "passive"))
    )
    (net (code "36") (name "OUT-VOLUME-CP1") (class "Default")
      (node (ref "VR1") (pin "2") (pinfunction "2_2") (pintype "passive"))
    )
    (net (code "37") (name "OUT-VOLUME-CP2") (class "Default")
      (node (ref "VR3") (pin "2") (pinfunction "2_2") (pintype "passive"))
    )
    (net (code "38") (name "OUT-VOLUME-CP3") (class "Default")
      (node (ref "VR4") (pin "2") (pinfunction "2_2") (pintype "passive"))
    )
    (net (code "39") (name "OUT_MIC1") (class "Default")
      (node (ref "C27") (pin "2") (pinfunction "2_2") (pintype "passive"))
      (node (ref "C30") (pin "1") (pinfunction "1_1") (pintype "passive"))
      (node (ref "R16") (pin "2") (pinfunction "2_2") (pintype "passive"))
      (node (ref "TP10") (pin "1") (pinfunction "1_1") (pintype "passive"))
      (node (ref "U6") (pin "1") (pinfunction "out_1") (pintype "passive"))
    )
    (net (code "40") (name "OUT_MIC2") (class "Default")
      (node (ref "C26") (pin "2") (pinfunction "2_2") (pintype "passive"))
      (node (ref "C37") (pin "1") (pinfunction "1_1") (pintype "passive"))
      (node (ref "R14") (pin "2") (pinfunction "2_2") (pintype "passive"))
      (node (ref "TP11") (pin "1") (pinfunction "1_1") (pintype "passive"))
      (node (ref "U6") (pin "7") (pinfunction "out_7") (pintype "passive"))
    )
    (net (code "41") (name "WS") (class "Default")
      (node (ref "U7") (pin "7") (pinfunction "LRCK_7") (pintype "passive"))
      (node (ref "U8") (pin "3") (pinfunction "LRCK_3") (pintype "passive"))
    )
  )
)
